# JlinkV9-SMTV2.net
KiCad netlist of a schematic drawn in Altium Designer
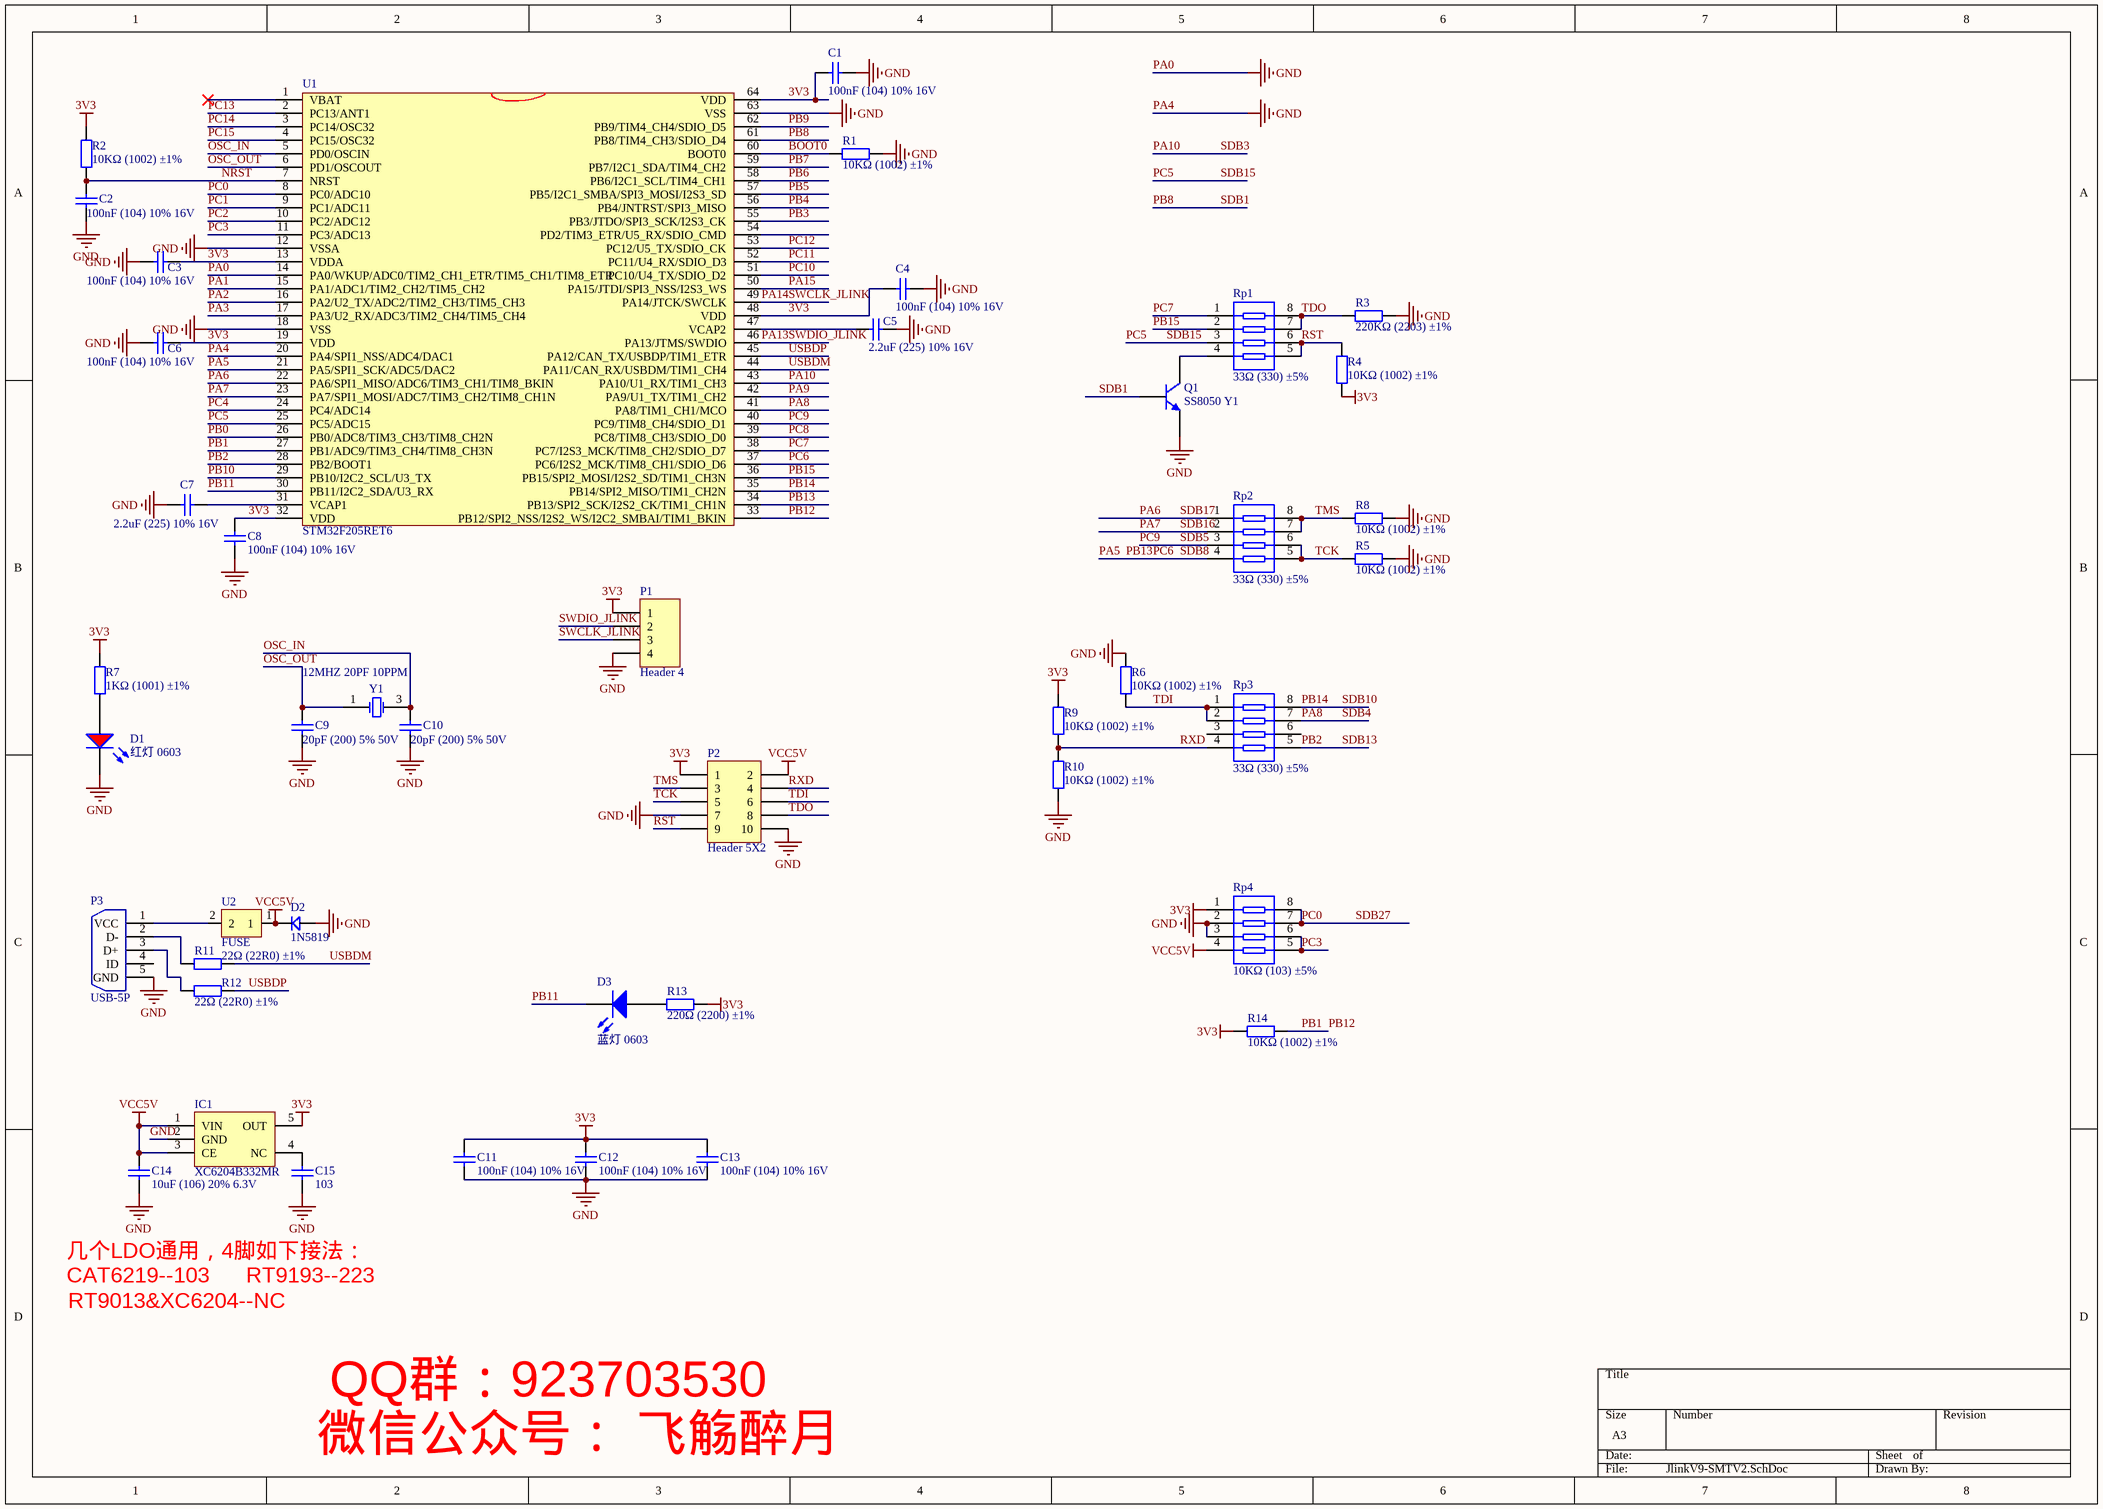
[diagram p0: JlinkV9-SMTV2.SchDoc]

(export (version "E")
  (design (tool "Eeschema 10.0.6"))
  (components
    (comp (ref "C1")
      (value "100nF (104) 10% 16V")
      (footprint "0402_C")
      (description "贴片电容")
      (libsource (lib "Miscellaneous Devices LC") (part "0402 100nF (104) 10% 16V"))
    )
    (comp (ref "C2")
      (value "100nF (104) 10% 16V")
      (footprint "0402_C")
      (description "贴片电容")
      (libsource (lib "Miscellaneous Devices LC") (part "0402 100nF (104) 10% 16V"))
    )
    (comp (ref "C3")
      (value "100nF (104) 10% 16V")
      (footprint "0402_C")
      (description "贴片电容")
      (libsource (lib "Miscellaneous Devices LC") (part "0402 100nF (104) 10% 16V"))
    )
    (comp (ref "C4")
      (value "100nF (104) 10% 16V")
      (footprint "0402_C")
      (description "贴片电容")
      (libsource (lib "Miscellaneous Devices LC") (part "0402 100nF (104) 10% 16V"))
    )
    (comp (ref "C5")
      (value "2.2uF (225) 10% 16V")
      (footprint "0603_C")
      (description "贴片电容")
      (libsource (lib "Miscellaneous Devices LC") (part "0603 2.2uF (225) 10% 16V"))
    )
    (comp (ref "C6")
      (value "100nF (104) 10% 16V")
      (footprint "0402_C")
      (description "贴片电容")
      (libsource (lib "Miscellaneous Devices LC") (part "0402 100nF (104) 10% 16V"))
    )
    (comp (ref "C7")
      (value "2.2uF (225) 10% 16V")
      (footprint "0603_C")
      (description "贴片电容")
      (libsource (lib "Miscellaneous Devices LC") (part "0603 2.2uF (225) 10% 16V"))
    )
    (comp (ref "C8")
      (value "100nF (104) 10% 16V")
      (footprint "0402_C")
      (description "贴片电容")
      (libsource (lib "Miscellaneous Devices LC") (part "0402 100nF (104) 10% 16V"))
    )
    (comp (ref "C9")
      (value "20pF (200) 5% 50V")
      (footprint "0402_C")
      (description "贴片电容")
      (libsource (lib "Miscellaneous Devices LC") (part "0402 20pF (200) 5% 50V"))
    )
    (comp (ref "C10")
      (value "20pF (200) 5% 50V")
      (footprint "0402_C")
      (description "贴片电容")
      (libsource (lib "Miscellaneous Devices LC") (part "0402 20pF (200) 5% 50V"))
    )
    (comp (ref "C11")
      (value "100nF (104) 10% 16V")
      (footprint "0402_C")
      (description "贴片电容")
      (libsource (lib "Miscellaneous Devices LC") (part "0402 100nF (104) 10% 16V"))
    )
    (comp (ref "C12")
      (value "100nF (104) 10% 16V")
      (footprint "0402_C")
      (description "贴片电容")
      (libsource (lib "Miscellaneous Devices LC") (part "0402 100nF (104) 10% 16V"))
    )
    (comp (ref "C13")
      (value "100nF (104) 10% 16V")
      (footprint "0402_C")
      (description "贴片电容")
      (libsource (lib "Miscellaneous Devices LC") (part "0402 100nF (104) 10% 16V"))
    )
    (comp (ref "C14")
      (value "10uF (106) 20% 6.3V")
      (footprint "0402_C")
      (description "贴片电容")
      (libsource (lib "Miscellaneous Devices LC") (part "0402 10uF (106) 20% 6.3V"))
    )
    (comp (ref "C15")
      (value "103")
      (footprint "0402_C")
      (description "贴片电容")
      (libsource (lib "Miscellaneous Devices LC") (part "0402 10nF (103) 10% 50V"))
    )
    (comp (ref "D1")
      (value "红灯 0603")
      (footprint "0603_LED_S1")
      (description "发光二极管")
      (libsource (lib "Miscellaneous Devices LC") (part "0603 红灯"))
    )
    (comp (ref "D2") (value "1N5819") (footprint "mypcblib:SOD-323") (libsource (lib "myschlib") (part "D")))
    (comp (ref "D3")
      (value "蓝灯 0603")
      (footprint "0603_LED_S1")
      (description "发光二极管")
      (libsource (lib "Miscellaneous Devices LC") (part "0603 蓝灯"))
    )
    (comp (ref "IC1")
      (value "XC6204B332MR")
      (footprint "SOT23-5L")
      (description "LDO")
      (fields (field (name "版权归属") "源创客"))
      (libsource (lib "myschlib") (part "LDO XC6204"))
    )
    (comp (ref "P1")
      (value "Header 4")
      (footprint "HDR1X4_SMD")
      (description "Header, 4-Pin")
      (fields (field (name "PUBLISHER") "Altium Limited"))
      (libsource (lib "myschlib") (part "Header 4"))
    )
    (comp (ref "P2")
      (value "Header 5X2")
      (footprint "mypcblib:HDR2X5_2.54_180H")
      (description "Header, 5-Pin, Dual row")
      (fields (field (name "PUBLISHER") "Altium Limited"))
      (libsource (lib "myschlib") (part "Header 5X2"))
    )
    (comp (ref "P3")
      (value "USB-5P")
      (footprint "MICRO_USB")
      (description "微型USB母座")
      (fields (field (name "版权归属") "源创客"))
      (libsource (lib "myschlib") (part "USB-5P"))
    )
    (comp (ref "Q1")
      (value "SS8050 Y1")
      (footprint "SOT-23(SOT-23-3)")
      (description "三极管")
      (libsource (lib "Miscellaneous Devices LC") (part "SOT-23 SS8050 Y1"))
    )
    (comp (ref "R1")
      (value "10KΩ (1002) ±1%")
      (footprint "0402_R")
      (description "贴片电阻")
      (libsource (lib "Miscellaneous Devices LC") (part "0402 10KΩ (1002) 1%"))
    )
    (comp (ref "R2")
      (value "10KΩ (1002) ±1%")
      (footprint "0402_R")
      (description "贴片电阻")
      (libsource (lib "") (part "0402 10KΩ (1002) 1%_1"))
    )
    (comp (ref "R3")
      (value "220KΩ (2203) ±1%")
      (footprint "0402_R")
      (description "贴片电阻")
      (libsource (lib "Miscellaneous Devices LC") (part "0402 220KΩ (2203) 1%"))
    )
    (comp (ref "R4")
      (value "10KΩ (1002) ±1%")
      (footprint "0402_R")
      (description "贴片电阻")
      (libsource (lib "") (part "0402 10KΩ (1002) 1%_1"))
    )
    (comp (ref "R5")
      (value "10KΩ (1002) ±1%")
      (footprint "0402_R")
      (description "贴片电阻")
      (libsource (lib "") (part "0402 10KΩ (1002) 1%_3"))
    )
    (comp (ref "R6")
      (value "10KΩ (1002) ±1%")
      (footprint "0402_R")
      (description "贴片电阻")
      (libsource (lib "") (part "0402 10KΩ (1002) 1%_2"))
    )
    (comp (ref "R7")
      (value "1KΩ (1001) ±1%")
      (footprint "0402_R")
      (description "贴片电阻")
      (libsource (lib "Miscellaneous Devices LC") (part "0402 1KΩ (1001) 1%"))
    )
    (comp (ref "R8")
      (value "10KΩ (1002) ±1%")
      (footprint "0402_R")
      (description "贴片电阻")
      (libsource (lib "Miscellaneous Devices LC") (part "0402 10KΩ (1002) 1%"))
    )
    (comp (ref "R9")
      (value "10KΩ (1002) ±1%")
      (footprint "0402_R")
      (description "贴片电阻")
      (libsource (lib "") (part "0402 10KΩ (1002) 1%_2"))
    )
    (comp (ref "R10")
      (value "10KΩ (1002) ±1%")
      (footprint "0402_R")
      (description "贴片电阻")
      (libsource (lib "") (part "0402 10KΩ (1002) 1%_2"))
    )
    (comp (ref "R11")
      (value "22Ω (22R0) ±1%")
      (footprint "0402_R")
      (description "贴片电阻")
      (libsource (lib "Miscellaneous Devices LC") (part "0402 22Ω (22R0) 1%"))
    )
    (comp (ref "R12")
      (value "22Ω (22R0) ±1%")
      (footprint "0402_R")
      (description "贴片电阻")
      (libsource (lib "Miscellaneous Devices LC") (part "0402 22Ω (22R0) 1%"))
    )
    (comp (ref "R13")
      (value "220Ω (2200) ±1%")
      (footprint "0402_R")
      (description "贴片电阻")
      (libsource (lib "Miscellaneous Devices LC") (part "0402 220Ω (2200) 1%"))
    )
    (comp (ref "R14")
      (value "10KΩ (1002) ±1%")
      (footprint "0402_R")
      (description "贴片电阻")
      (libsource (lib "Miscellaneous Devices LC") (part "0402 10KΩ (1002) 1%"))
    )
    (comp (ref "Rp1")
      (value "33Ω (330) ±5%")
      (footprint "0402_Rx4")
      (description "贴片排阻")
      (libsource (lib "Miscellaneous Devices LC") (part "0402*4 33Ω (330) 5%"))
    )
    (comp (ref "Rp2")
      (value "33Ω (330) ±5%")
      (footprint "0402_Rx4")
      (description "贴片排阻")
      (libsource (lib "Miscellaneous Devices LC") (part "0402*4 33Ω (330) 5%"))
    )
    (comp (ref "Rp3")
      (value "33Ω (330) ±5%")
      (footprint "0402_Rx4")
      (description "贴片排阻")
      (libsource (lib "Miscellaneous Devices LC") (part "0402*4 33Ω (330) 5%"))
    )
    (comp (ref "Rp4")
      (value "10KΩ (103) ±5%")
      (footprint "0402_Rx4")
      (description "贴片排阻")
      (libsource (lib "Miscellaneous Devices LC") (part "0402*4 10KΩ (103) 5%"))
    )
    (comp (ref "U1")
      (value "STM32F205RET6")
      (footprint "STM-LQFP64_M")
      (libsource (lib "JlinkV9-SMTV2") (part "STM32F205RET6"))
    )
    (comp (ref "U2") (value "FUSE") (footprint "mypcblib:0603_C") (libsource (lib "myschlib") (part "FUSE")))
    (comp (ref "Y1")
      (value "12MHZ 20PF 10PPM")
      (footprint "SMD-3225_4P")
      (description "贴片晶振")
      (libsource (lib "Miscellaneous Devices LC") (part "SMD-3225_4P  12MHZ 20PF 10PPM"))
    )
  )
  (nets
    (net (code "1") (name "/BOOT0") (class "Default")
      (node (ref "R1") (pin "1") (pinfunction "1_1") (pintype "passive"))
      (node (ref "U1") (pin "60") (pinfunction "BOOT0_60") (pintype "passive"))
    )
    (net (code "2") (name "/NRST") (class "Default")
      (node (ref "C2") (pin "2") (pinfunction "2_2") (pintype "passive"))
      (node (ref "R2") (pin "1") (pinfunction "1_1") (pintype "passive"))
      (node (ref "U1") (pin "7") (pinfunction "NRST_7") (pintype "passive"))
    )
    (net (code "3") (name "/OSC_IN") (class "Default")
      (node (ref "C10") (pin "2") (pinfunction "2_2") (pintype "passive"))
      (node (ref "U1") (pin "5") (pinfunction "PD0/OSCIN_5") (pintype "passive"))
      (node (ref "Y1") (pin "3") (pinfunction "OSC2_3") (pintype "passive"))
    )
    (net (code "4") (name "/OSC_OUT") (class "Default")
      (node (ref "C9") (pin "2") (pinfunction "2_2") (pintype "passive"))
      (node (ref "U1") (pin "6") (pinfunction "PD1/OSCOUT_6") (pintype "passive"))
      (node (ref "Y1") (pin "1") (pinfunction "OSC1_1") (pintype "passive"))
    )
    (net (code "5") (name "/PA1") (class "Default")
      (node (ref "U1") (pin "15") (pinfunction "PA1/ADC1/TIM2_CH2/TIM5_CH2_15") (pintype "passive"))
    )
    (net (code "6") (name "/PA2") (class "Default")
      (node (ref "U1") (pin "16") (pinfunction "PA2/U2_TX/ADC2/TIM2_CH3/TIM5_CH3_16") (pintype "passive"))
    )
    (net (code "7") (name "/PA3") (class "Default")
      (node (ref "U1") (pin "17") (pinfunction "PA3/U2_RX/ADC3/TIM2_CH4/TIM5_CH4_17") (pintype "passive"))
    )
    (net (code "8") (name "/PA5") (class "Default")
      (node (ref "Rp2") (pin "4") (pinfunction "4_4") (pintype "passive"))
      (node (ref "U1") (pin "21") (pinfunction "PA5/SPI1_SCK/ADC5/DAC2_21") (pintype "passive"))
      (node (ref "U1") (pin "34") (pinfunction "PB13/SPI2_SCK/I2S2_CK/TIM1_CH1N_34") (pintype "passive"))
      (node (ref "U1") (pin "37") (pinfunction "PC6/I2S2_MCK/TIM8_CH1/SDIO_D6_37") (pintype "passive"))
    )
    (net (code "9") (name "/PA6") (class "Default")
      (node (ref "Rp2") (pin "1") (pinfunction "1_1") (pintype "passive"))
      (node (ref "U1") (pin "22") (pinfunction "PA6/SPI1_MISO/ADC6/TIM3_CH1/TIM8_BKIN_22") (pintype "passive"))
    )
    (net (code "10") (name "/PA7") (class "Default")
      (node (ref "Rp2") (pin "2") (pinfunction "2_2") (pintype "passive"))
      (node (ref "U1") (pin "23") (pinfunction "PA7/SPI1_MOSI/ADC7/TIM3_CH2/TIM8_CH1N_23") (pintype "passive"))
    )
    (net (code "11") (name "/PA8") (class "Default")
      (node (ref "Rp3") (pin "7") (pinfunction "7_7") (pintype "passive"))
      (node (ref "U1") (pin "41") (pinfunction "PA8/TIM1_CH1/MCO_41") (pintype "passive"))
    )
    (net (code "12") (name "/PA9") (class "Default")
      (node (ref "U1") (pin "42") (pinfunction "PA9/U1_TX/TIM1_CH2_42") (pintype "passive"))
    )
    (net (code "13") (name "/PA10") (class "Default")
      (node (ref "U1") (pin "43") (pinfunction "PA10/U1_RX/TIM1_CH3_43") (pintype "passive"))
    )
    (net (code "14") (name "/PA13") (class "Default")
      (node (ref "P1") (pin "2") (pinfunction "2_2") (pintype "passive"))
      (node (ref "U1") (pin "46") (pinfunction "PA13/JTMS/SWDIO_46") (pintype "passive"))
    )
    (net (code "15") (name "/PA14") (class "Default")
      (node (ref "P1") (pin "3") (pinfunction "3_3") (pintype "passive"))
      (node (ref "U1") (pin "49") (pinfunction "PA14/JTCK/SWCLK_49") (pintype "passive"))
    )
    (net (code "16") (name "/PA15") (class "Default")
      (node (ref "U1") (pin "50") (pinfunction "PA15/JTDI/SPI3_NSS/I2S3_WS_50") (pintype "passive"))
    )
    (net (code "17") (name "/PB0") (class "Default")
      (node (ref "U1") (pin "26") (pinfunction "PB0/ADC8/TIM3_CH3/TIM8_CH2N_26") (pintype "passive"))
    )
    (net (code "18") (name "/PB1") (class "Default")
      (node (ref "R14") (pin "2") (pinfunction "2_2") (pintype "passive"))
      (node (ref "U1") (pin "27") (pinfunction "PB1/ADC9/TIM3_CH4/TIM8_CH3N_27") (pintype "passive"))
      (node (ref "U1") (pin "33") (pinfunction "PB12/SPI2_NSS/I2S2_WS/I2C2_SMBAI/TIM1_BKIN_33") (pintype "passive"))
    )
    (net (code "19") (name "/PB2") (class "Default")
      (node (ref "Rp3") (pin "5") (pinfunction "5_5") (pintype "passive"))
      (node (ref "U1") (pin "28") (pinfunction "PB2/BOOT1_28") (pintype "passive"))
    )
    (net (code "20") (name "/PB3") (class "Default")
      (node (ref "U1") (pin "55") (pinfunction "PB3/JTDO/SPI3_SCK/I2S3_CK_55") (pintype "passive"))
    )
    (net (code "21") (name "/PB4") (class "Default")
      (node (ref "U1") (pin "56") (pinfunction "PB4/JNTRST/SPI3_MISO_56") (pintype "passive"))
    )
    (net (code "22") (name "/PB5") (class "Default")
      (node (ref "U1") (pin "57") (pinfunction "PB5/I2C1_SMBA/SPI3_MOSI/I2S3_SD_57") (pintype "passive"))
    )
    (net (code "23") (name "/PB6") (class "Default")
      (node (ref "U1") (pin "58") (pinfunction "PB6/I2C1_SCL/TIM4_CH1_58") (pintype "passive"))
    )
    (net (code "24") (name "/PB7") (class "Default")
      (node (ref "U1") (pin "59") (pinfunction "PB7/I2C1_SDA/TIM4_CH2_59") (pintype "passive"))
    )
    (net (code "25") (name "/PB8") (class "Default")
      (node (ref "Q1") (pin "1") (pinfunction "B_1") (pintype "passive"))
      (node (ref "U1") (pin "61") (pinfunction "PB8/TIM4_CH3/SDIO_D4_61") (pintype "passive"))
    )
    (net (code "26") (name "/PB9") (class "Default")
      (node (ref "U1") (pin "62") (pinfunction "PB9/TIM4_CH4/SDIO_D5_62") (pintype "passive"))
    )
    (net (code "27") (name "/PB10") (class "Default")
      (node (ref "U1") (pin "29") (pinfunction "PB10/I2C2_SCL/U3_TX_29") (pintype "passive"))
    )
    (net (code "28") (name "/PB11") (class "Default")
      (node (ref "D3") (pin "K") (pinfunction "K_K") (pintype "passive"))
      (node (ref "U1") (pin "30") (pinfunction "PB11/I2C2_SDA/U3_RX_30") (pintype "passive"))
    )
    (net (code "29") (name "/PB14") (class "Default")
      (node (ref "Rp3") (pin "8") (pinfunction "8_8") (pintype "passive"))
      (node (ref "U1") (pin "35") (pinfunction "PB14/SPI2_MISO/TIM1_CH2N_35") (pintype "passive"))
    )
    (net (code "30") (name "/PB15") (class "Default")
      (node (ref "Rp1") (pin "2") (pinfunction "2_2") (pintype "passive"))
      (node (ref "U1") (pin "36") (pinfunction "PB15/SPI2_MOSI/I2S2_SD/TIM1_CH3N_36") (pintype "passive"))
    )
    (net (code "31") (name "/PC0") (class "Default")
      (node (ref "Rp4") (pin "7") (pinfunction "7_7") (pintype "passive"))
      (node (ref "Rp4") (pin "8") (pinfunction "8_8") (pintype "passive"))
      (node (ref "U1") (pin "8") (pinfunction "PC0/ADC10_8") (pintype "passive"))
    )
    (net (code "32") (name "/PC1") (class "Default")
      (node (ref "U1") (pin "9") (pinfunction "PC1/ADC11_9") (pintype "passive"))
    )
    (net (code "33") (name "/PC2") (class "Default")
      (node (ref "U1") (pin "10") (pinfunction "PC2/ADC12_10") (pintype "passive"))
    )
    (net (code "34") (name "/PC3") (class "Default")
      (node (ref "Rp4") (pin "5") (pinfunction "5_5") (pintype "passive"))
      (node (ref "Rp4") (pin "6") (pinfunction "6_6") (pintype "passive"))
      (node (ref "U1") (pin "11") (pinfunction "PC3/ADC13_11") (pintype "passive"))
    )
    (net (code "35") (name "/PC4") (class "Default")
      (node (ref "U1") (pin "24") (pinfunction "PC4/ADC14_24") (pintype "passive"))
    )
    (net (code "36") (name "/PC5") (class "Default")
      (node (ref "Rp1") (pin "3") (pinfunction "3_3") (pintype "passive"))
      (node (ref "U1") (pin "25") (pinfunction "PC5/ADC15_25") (pintype "passive"))
    )
    (net (code "37") (name "/PC7") (class "Default")
      (node (ref "Rp1") (pin "1") (pinfunction "1_1") (pintype "passive"))
      (node (ref "U1") (pin "38") (pinfunction "PC7/I2S3_MCK/TIM8_CH2/SDIO_D7_38") (pintype "passive"))
    )
    (net (code "38") (name "/PC8") (class "Default")
      (node (ref "U1") (pin "39") (pinfunction "PC8/TIM8_CH3/SDIO_D0_39") (pintype "passive"))
    )
    (net (code "39") (name "/PC9") (class "Default")
      (node (ref "Rp2") (pin "3") (pinfunction "3_3") (pintype "passive"))
      (node (ref "U1") (pin "40") (pinfunction "PC9/TIM8_CH4/SDIO_D1_40") (pintype "passive"))
    )
    (net (code "40") (name "/PC10") (class "Default")
      (node (ref "U1") (pin "51") (pinfunction "PC10/U4_TX/SDIO_D2_51") (pintype "passive"))
    )
    (net (code "41") (name "/PC11") (class "Default")
      (node (ref "U1") (pin "52") (pinfunction "PC11/U4_RX/SDIO_D3_52") (pintype "passive"))
    )
    (net (code "42") (name "/PC12") (class "Default")
      (node (ref "U1") (pin "53") (pinfunction "PC12/U5_TX/SDIO_CK_53") (pintype "passive"))
    )
    (net (code "43") (name "/PC13") (class "Default")
      (node (ref "U1") (pin "2") (pinfunction "PC13/ANT1_2") (pintype "passive"))
    )
    (net (code "44") (name "/PC14") (class "Default")
      (node (ref "U1") (pin "3") (pinfunction "PC14/OSC32_3") (pintype "passive"))
    )
    (net (code "45") (name "/PC15") (class "Default")
      (node (ref "U1") (pin "4") (pinfunction "PC15/OSC32_4") (pintype "passive"))
    )
    (net (code "46") (name "/RST") (class "Default")
      (node (ref "P2") (pin "9") (pinfunction "9_9") (pintype "passive"))
      (node (ref "R4") (pin "2") (pinfunction "2_2") (pintype "passive"))
      (node (ref "Rp1") (pin "5") (pinfunction "5_5") (pintype "passive"))
      (node (ref "Rp1") (pin "6") (pinfunction "6_6") (pintype "passive"))
    )
    (net (code "47") (name "/RXD") (class "Default")
      (node (ref "P2") (pin "4") (pinfunction "4_4") (pintype "passive"))
      (node (ref "R10") (pin "1") (pinfunction "1_1") (pintype "passive"))
      (node (ref "R9") (pin "2") (pinfunction "2_2") (pintype "passive"))
      (node (ref "Rp3") (pin "4") (pinfunction "4_4") (pintype "passive"))
    )
    (net (code "48") (name "/TCK") (class "Default")
      (node (ref "P2") (pin "5") (pinfunction "5_5") (pintype "passive"))
      (node (ref "R5") (pin "2") (pinfunction "2_2") (pintype "passive"))
      (node (ref "Rp2") (pin "5") (pinfunction "5_5") (pintype "passive"))
      (node (ref "Rp2") (pin "6") (pinfunction "6_6") (pintype "passive"))
    )
    (net (code "49") (name "/TDI") (class "Default")
      (node (ref "P2") (pin "6") (pinfunction "6_6") (pintype "passive"))
      (node (ref "R6") (pin "2") (pinfunction "2_2") (pintype "passive"))
      (node (ref "Rp3") (pin "1") (pinfunction "1_1") (pintype "passive"))
      (node (ref "Rp3") (pin "2") (pinfunction "2_2") (pintype "passive"))
    )
    (net (code "50") (name "/TDO") (class "Default")
      (node (ref "P2") (pin "8") (pinfunction "8_8") (pintype "passive"))
      (node (ref "R3") (pin "2") (pinfunction "2_2") (pintype "passive"))
      (node (ref "Rp1") (pin "7") (pinfunction "7_7") (pintype "passive"))
      (node (ref "Rp1") (pin "8") (pinfunction "8_8") (pintype "passive"))
    )
    (net (code "51") (name "/TMS") (class "Default")
      (node (ref "P2") (pin "3") (pinfunction "3_3") (pintype "passive"))
      (node (ref "R8") (pin "1") (pinfunction "1_1") (pintype "passive"))
      (node (ref "Rp2") (pin "7") (pinfunction "7_7") (pintype "passive"))
      (node (ref "Rp2") (pin "8") (pinfunction "8_8") (pintype "passive"))
    )
    (net (code "52") (name "/USBDM") (class "Default")
      (node (ref "R11") (pin "2") (pinfunction "2_2") (pintype "passive"))
      (node (ref "U1") (pin "44") (pinfunction "PA11/CAN_RX/USBDM/TIM1_CH4_44") (pintype "passive"))
    )
    (net (code "53") (name "/USBDP") (class "Default")
      (node (ref "R12") (pin "2") (pinfunction "2_2") (pintype "passive"))
      (node (ref "U1") (pin "45") (pinfunction "PA12/CAN_TX/USBDP/TIM1_ETR_45") (pintype "passive"))
    )
    (net (code "54") (name "3V3") (class "Default")
      (node (ref "C1") (pin "1") (pinfunction "1_1") (pintype "passive"))
      (node (ref "C11") (pin "2") (pinfunction "2_2") (pintype "passive"))
      (node (ref "C12") (pin "2") (pinfunction "2_2") (pintype "passive"))
      (node (ref "C13") (pin "2") (pinfunction "2_2") (pintype "passive"))
      (node (ref "C3") (pin "2") (pinfunction "2_2") (pintype "passive"))
      (node (ref "C4") (pin "1") (pinfunction "1_1") (pintype "passive"))
      (node (ref "C6") (pin "2") (pinfunction "2_2") (pintype "passive"))
      (node (ref "C8") (pin "2") (pinfunction "2_2") (pintype "passive"))
      (node (ref "IC1") (pin "5") (pinfunction "OUT_5") (pintype "passive"))
      (node (ref "P1") (pin "1") (pinfunction "1_1") (pintype "passive"))
      (node (ref "P2") (pin "1") (pinfunction "1_1") (pintype "passive"))
      (node (ref "R13") (pin "2") (pinfunction "2_2") (pintype "passive"))
      (node (ref "R14") (pin "1") (pinfunction "1_1") (pintype "passive"))
      (node (ref "R2") (pin "2") (pinfunction "2_2") (pintype "passive"))
      (node (ref "R4") (pin "1") (pinfunction "1_1") (pintype "passive"))
      (node (ref "R7") (pin "2") (pinfunction "2_2") (pintype "passive"))
      (node (ref "R9") (pin "1") (pinfunction "1_1") (pintype "passive"))
      (node (ref "Rp4") (pin "1") (pinfunction "1_1") (pintype "passive"))
      (node (ref "U1") (pin "13") (pinfunction "VDDA_13") (pintype "passive"))
      (node (ref "U1") (pin "19") (pinfunction "VDD_19") (pintype "passive"))
      (node (ref "U1") (pin "32") (pinfunction "VDD_32") (pintype "passive"))
      (node (ref "U1") (pin "48") (pinfunction "VDD_48") (pintype "passive"))
      (node (ref "U1") (pin "64") (pinfunction "VDD_64") (pintype "passive"))
    )
    (net (code "55") (name "GND") (class "Default")
      (node (ref "C1") (pin "2") (pinfunction "2_2") (pintype "passive"))
      (node (ref "C10") (pin "1") (pinfunction "1_1") (pintype "passive"))
      (node (ref "C11") (pin "1") (pinfunction "1_1") (pintype "passive"))
      (node (ref "C12") (pin "1") (pinfunction "1_1") (pintype "passive"))
      (node (ref "C13") (pin "1") (pinfunction "1_1") (pintype "passive"))
      (node (ref "C14") (pin "1") (pinfunction "1_1") (pintype "passive"))
      (node (ref "C15") (pin "1") (pinfunction "1_1") (pintype "passive"))
      (node (ref "C2") (pin "1") (pinfunction "1_1") (pintype "passive"))
      (node (ref "C3") (pin "1") (pinfunction "1_1") (pintype "passive"))
      (node (ref "C4") (pin "2") (pinfunction "2_2") (pintype "passive"))
      (node (ref "C5") (pin "2") (pinfunction "2_2") (pintype "passive"))
      (node (ref "C6") (pin "1") (pinfunction "1_1") (pintype "passive"))
      (node (ref "C7") (pin "1") (pinfunction "1_1") (pintype "passive"))
      (node (ref "C8") (pin "1") (pinfunction "1_1") (pintype "passive"))
      (node (ref "C9") (pin "1") (pinfunction "1_1") (pintype "passive"))
      (node (ref "D1") (pin "K") (pinfunction "K_K") (pintype "passive"))
      (node (ref "D2") (pin "1") (pintype "passive"))
      (node (ref "IC1") (pin "2") (pinfunction "GND_2") (pintype "passive"))
      (node (ref "P1") (pin "4") (pinfunction "4_4") (pintype "passive"))
      (node (ref "P2") (pin "10") (pinfunction "10_10") (pintype "passive"))
      (node (ref "P2") (pin "7") (pinfunction "7_7") (pintype "passive"))
      (node (ref "P3") (pin "5") (pinfunction "GND_5") (pintype "passive"))
      (node (ref "Q1") (pin "2") (pinfunction "E_2") (pintype "passive"))
      (node (ref "R1") (pin "2") (pinfunction "2_2") (pintype "passive"))
      (node (ref "R10") (pin "2") (pinfunction "2_2") (pintype "passive"))
      (node (ref "R3") (pin "1") (pinfunction "1_1") (pintype "passive"))
      (node (ref "R5") (pin "1") (pinfunction "1_1") (pintype "passive"))
      (node (ref "R6") (pin "1") (pinfunction "1_1") (pintype "passive"))
      (node (ref "R8") (pin "2") (pinfunction "2_2") (pintype "passive"))
      (node (ref "Rp4") (pin "2") (pinfunction "2_2") (pintype "passive"))
      (node (ref "Rp4") (pin "3") (pinfunction "3_3") (pintype "passive"))
      (node (ref "U1") (pin "12") (pinfunction "VSSA_12") (pintype "passive"))
      (node (ref "U1") (pin "14") (pinfunction "PA0/WKUP/ADC0/TIM2_CH1_ETR/TIM5_CH1/TIM8_ETR_14") (pintype "passive"))
      (node (ref "U1") (pin "18") (pinfunction "VSS_18") (pintype "passive"))
      (node (ref "U1") (pin "20") (pinfunction "PA4/SPI1_NSS/ADC4/DAC1_20") (pintype "passive"))
      (node (ref "U1") (pin "63") (pinfunction "VSS_63") (pintype "passive"))
    )
    (net (code "56") (name "Net-(D1-PadA)") (class "Default")
      (node (ref "D1") (pin "A") (pinfunction "A_A") (pintype "passive"))
      (node (ref "R7") (pin "1") (pinfunction "1_1") (pintype "passive"))
    )
    (net (code "57") (name "Net-(D3-PadA)") (class "Default")
      (node (ref "D3") (pin "A") (pinfunction "A_A") (pintype "passive"))
      (node (ref "R13") (pin "1") (pinfunction "1_1") (pintype "passive"))
    )
    (net (code "58") (name "Net-(IC1-NC)") (class "Default")
      (node (ref "C15") (pin "2") (pinfunction "2_2") (pintype "passive"))
      (node (ref "IC1") (pin "4") (pinfunction "NC_4") (pintype "passive"))
    )
    (net (code "59") (name "Net-(P3-D+)") (class "Default")
      (node (ref "P3") (pin "3") (pinfunction "D+_3") (pintype "passive"))
      (node (ref "R12") (pin "1") (pinfunction "1_1") (pintype "passive"))
    )
    (net (code "60") (name "Net-(P3-D-)") (class "Default")
      (node (ref "P3") (pin "2") (pinfunction "D-_2") (pintype "passive"))
      (node (ref "R11") (pin "1") (pinfunction "1_1") (pintype "passive"))
    )
    (net (code "61") (name "Net-(P3-VCC)") (class "Default")
      (node (ref "P3") (pin "1") (pinfunction "VCC_1") (pintype "passive"))
      (node (ref "U2") (pin "2") (pinfunction "2_2") (pintype "passive"))
    )
    (net (code "62") (name "Net-(Q1-C)") (class "Default")
      (node (ref "Q1") (pin "3") (pinfunction "C_3") (pintype "passive"))
      (node (ref "Rp1") (pin "4") (pinfunction "4_4") (pintype "passive"))
    )
    (net (code "63") (name "Net-(U1-VCAP1)") (class "Default")
      (node (ref "C7") (pin "2") (pinfunction "2_2") (pintype "passive"))
      (node (ref "U1") (pin "31") (pinfunction "VCAP1_31") (pintype "passive"))
    )
    (net (code "64") (name "Net-(U1-VCAP2)") (class "Default")
      (node (ref "C5") (pin "1") (pinfunction "1_1") (pintype "passive"))
      (node (ref "U1") (pin "47") (pinfunction "VCAP2_47") (pintype "passive"))
    )
    (net (code "65") (name "VCC5V") (class "Default")
      (node (ref "C14") (pin "2") (pinfunction "2_2") (pintype "passive"))
      (node (ref "D2") (pin "2") (pintype "passive"))
      (node (ref "IC1") (pin "1") (pinfunction "VIN_1") (pintype "passive"))
      (node (ref "IC1") (pin "3") (pinfunction "CE_3") (pintype "passive"))
      (node (ref "P2") (pin "2") (pinfunction "2_2") (pintype "passive"))
      (node (ref "Rp4") (pin "4") (pinfunction "4_4") (pintype "passive"))
      (node (ref "U2") (pin "1") (pinfunction "1_1") (pintype "passive"))
    )
    (net (code "66") (name "unconnected-(P3-ID-Pad4)") (class "Default")
      (node (ref "P3") (pin "4") (pinfunction "ID_4") (pintype "passive"))
    )
    (net (code "67") (name "unconnected-(Rp3-Pad3)") (class "Default")
      (node (ref "Rp3") (pin "3") (pinfunction "3_3") (pintype "passive"))
    )
    (net (code "68") (name "unconnected-(Rp3-Pad6)") (class "Default")
      (node (ref "Rp3") (pin "6") (pinfunction "6_6") (pintype "passive"))
    )
    (net (code "69") (name "unconnected-(U1-PD2{slash}TIM3_ETR{slash}U5_RX{slash}SDIO_CMD-Pad54)") (class "Default")
      (node (ref "U1") (pin "54") (pinfunction "PD2/TIM3_ETR/U5_RX/SDIO_CMD_54") (pintype "passive"))
    )
    (net (code "70") (name "unconnected-(U1-VBAT-Pad1)") (class "Default")
      (node (ref "U1") (pin "1") (pinfunction "VBAT_1") (pintype "passive+no_connect"))
    )
  )
)
